# 7805.net
KiCad netlist of a schematic drawn in Altium Designer
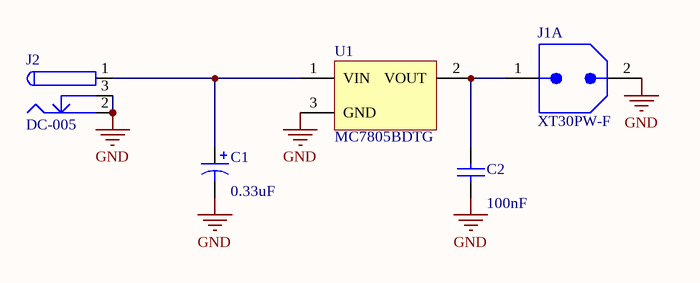
[diagram p0: 7805.SchDoc]

(export (version "E")
  (design (tool "Eeschema 10.0.6"))
  (components
    (comp (ref "C1")
      (value "0.33uF")
      (footprint "THT Electrolythic 5x11x2mm")
      (description "Generic THT Electrolytic capacitor")
      (libsource (lib "C6H6`s Vault") (part "Generic THT Electrolytic capacitor"))
    )
    (comp (ref "C2")
      (value "100nF")
      (footprint "Generic THT Ceramic -Footprint-2")
      (description "Generic Thruhole Ceramic Disc Capacitor")
      (fields (field (name "Comment") "Generic THT Ceramic"))
      (libsource (lib "C6H6`s Vault") (part "Generic Radial ceramic"))
    )
    (comp (ref "J1")
      (value "XT30PW-F")
      (footprint "XT30 Female PCB Mount-Footprint-1")
      (description "XT30 BAT Connector Female PCB Mount")
      (libsource (lib "C6H6`s Vault") (part "XT30 PCBMOUNT"))
    )
    (comp (ref "J2")
      (value "DC-005")
      (footprint "DC-0005-Footprint-1")
      (description "DC Adapter Jack 2.0mm")
      (libsource (lib "C6H6`s Vault") (part "DC-0005"))
    )
    (comp (ref "U1")
      (value "MC7805BDTG")
      (footprint "DPAK229P991X238-3M")
      (libsource (lib "C6H6`s Vault") (part "MC7805BDTG"))
    )
  )
  (nets
    (net (code "1") (name "GND") (class "Default")
      (node (ref "C1") (pin "2") (pinfunction "2_2") (pintype "passive"))
      (node (ref "C2") (pin "1") (pinfunction "1_1") (pintype "passive"))
      (node (ref "J1") (pin "2") (pinfunction "2_2") (pintype "passive"))
      (node (ref "J2") (pin "2") (pinfunction "2_2") (pintype "power_in"))
      (node (ref "J2") (pin "3") (pinfunction "3_3") (pintype "power_in"))
      (node (ref "U1") (pin "3") (pinfunction "GND_3") (pintype "passive"))
    )
    (net (code "2") (name "Net-(U1-VIN)") (class "Default")
      (node (ref "C1") (pin "1") (pinfunction "1_1") (pintype "passive"))
      (node (ref "J2") (pin "1") (pinfunction "1_1") (pintype "power_in"))
      (node (ref "U1") (pin "1") (pinfunction "VIN_1") (pintype "passive"))
    )
    (net (code "3") (name "Net-(U1-VOUT)") (class "Default")
      (node (ref "C2") (pin "2") (pinfunction "2_2") (pintype "passive"))
      (node (ref "J1") (pin "1") (pinfunction "1_1") (pintype "passive"))
      (node (ref "U1") (pin "2") (pinfunction "VOUT_2") (pintype "passive"))
    )
  )
)
